# MODULE_CONTROL.net
KiCad netlist of a schematic drawn in Altium Designer
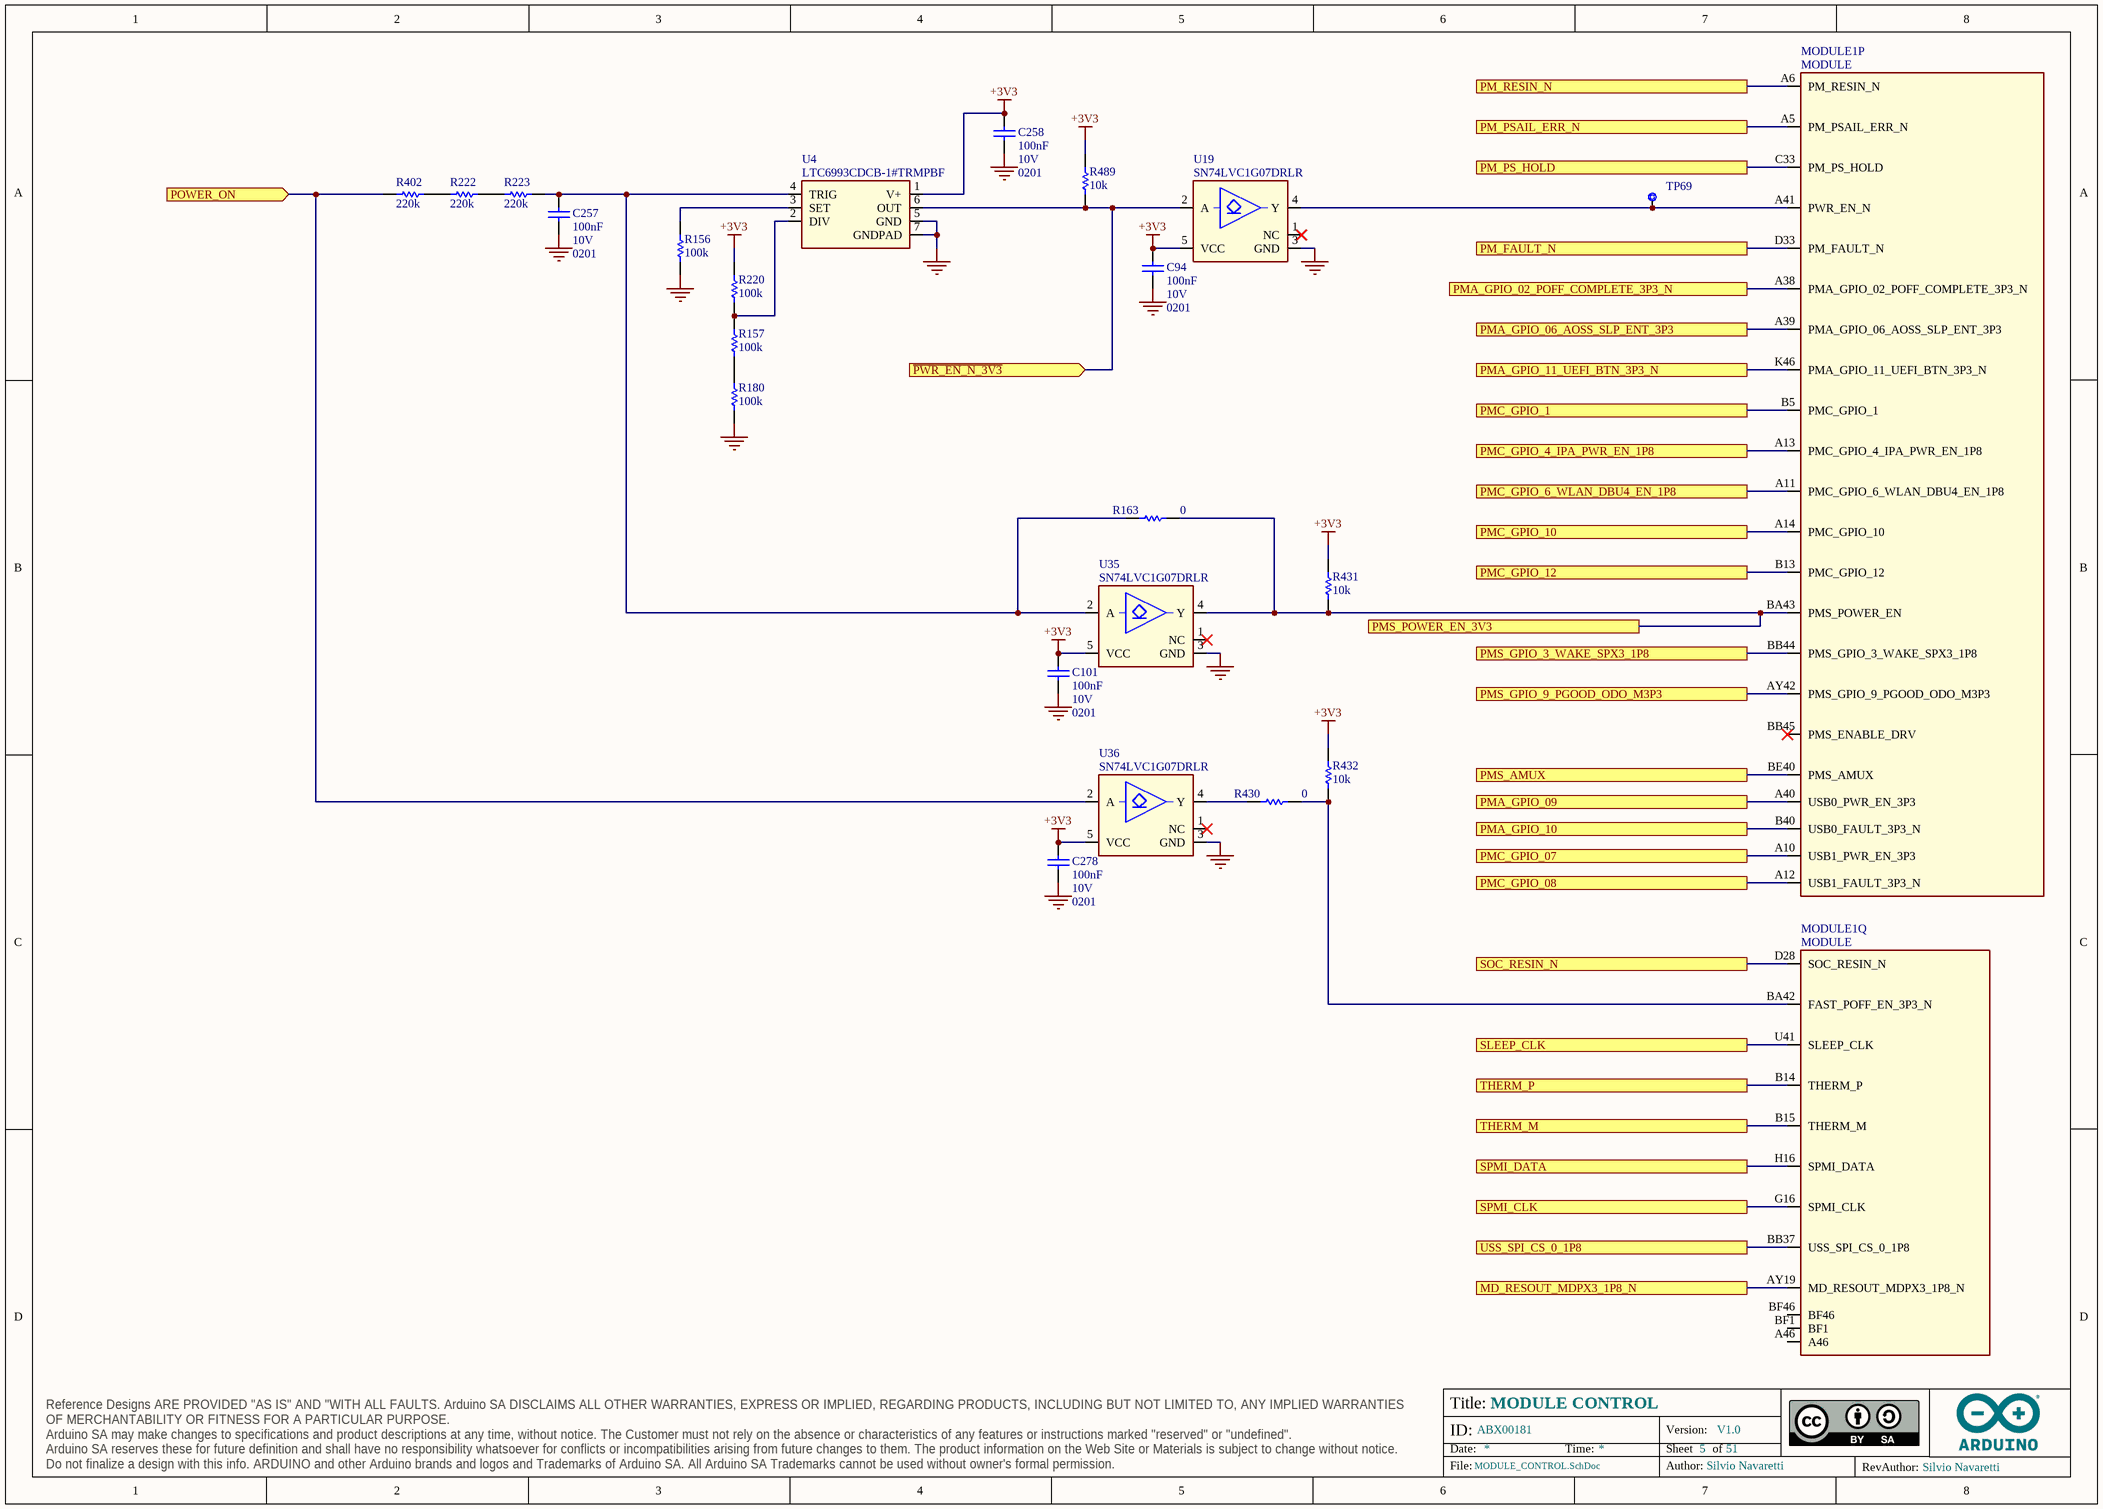
[diagram p0: MODULE_CONTROL.SchDoc]

(export (version "E")
  (design (tool "Eeschema 10.0.6"))
  (components
    (comp (ref "C94")
      (value "100nF")
      (footprint "CAP-0201")
      (description "CAP CHIP 0201 100nF 10% 10V X5R")
      (fields
        (field (name "PART NUMBER") "CL03A104KP3NNNC")
        (field (name "MANUFACTURER") "Samsung Electro-Mechanics")
        (field (name "VOLTAGE") "10V")
        (field (name "CASE CODE (IMPERIAL)") "0201")
      )
      (libsource (lib "Clean") (part "CAP"))
    )
    (comp (ref "C101")
      (value "100nF")
      (footprint "CAP-0201")
      (description "CAP CHIP 0201 100nF 10% 10V X5R")
      (fields
        (field (name "PART NUMBER") "CL03A104KP3NNNC")
        (field (name "MANUFACTURER") "Samsung Electro-Mechanics")
        (field (name "VOLTAGE") "10V")
        (field (name "CASE CODE (IMPERIAL)") "0201")
      )
      (libsource (lib "Clean") (part "CAP"))
    )
    (comp (ref "C257")
      (value "100nF")
      (footprint "CAP-0201")
      (description "CAP CHIP 0201 100nF 10% 10V X5R")
      (fields
        (field (name "PART NUMBER") "CL03A104KP3NNNC")
        (field (name "MANUFACTURER") "Samsung Electro-Mechanics")
        (field (name "VOLTAGE") "10V")
        (field (name "CASE CODE (IMPERIAL)") "0201")
      )
      (libsource (lib "Clean") (part "CAP"))
    )
    (comp (ref "C258")
      (value "100nF")
      (footprint "CAP-0201")
      (description "CAP CHIP 0201 100nF 10% 10V X5R")
      (fields
        (field (name "PART NUMBER") "CL03A104KP3NNNC")
        (field (name "MANUFACTURER") "Samsung Electro-Mechanics")
        (field (name "VOLTAGE") "10V")
        (field (name "CASE CODE (IMPERIAL)") "0201")
      )
      (libsource (lib "Clean") (part "CAP"))
    )
    (comp (ref "C278")
      (value "100nF")
      (footprint "CAP-0201")
      (description "CAP CHIP 0201 100nF 10% 10V X5R")
      (fields
        (field (name "PART NUMBER") "CL03A104KP3NNNC")
        (field (name "MANUFACTURER") "Samsung Electro-Mechanics")
        (field (name "VOLTAGE") "10V")
        (field (name "CASE CODE (IMPERIAL)") "0201")
      )
      (libsource (lib "Clean") (part "CAP"))
    )
    (comp (ref "MODULE1")
      (value "MODULE")
      (footprint "MODULE")
      (description "MODULE BGA 1883 balls 57.5x57.5mm")
      (fields (field (name "MANUFACTURER") "Qualcomm") (field (name "PART NUMBER") "MODULE BGA"))
      (libsource (lib "Clean") (part "MODULE"))
    )
    (comp (ref "R156")
      (value "100k")
      (footprint "RES-0201")
      (description "RES CHIP 0201 100k 1% 1/20W")
      (fields (field (name "POWER") "50mW") (field (name "TOLERANCE") "1%"))
      (libsource (lib "Clean") (part "RES"))
    )
    (comp (ref "R157")
      (value "100k")
      (footprint "RES-0201")
      (description "RES CHIP 0201 100k 1% 1/20W")
      (fields (field (name "POWER") "50mW") (field (name "TOLERANCE") "1%"))
      (libsource (lib "Clean") (part "RES"))
    )
    (comp (ref "R163")
      (value "0")
      (footprint "RES-0201")
      (description "RES CHIP 0201 0R")
      (fields (field (name "MANUFACTURER") "Vishay") (field (name "PART NUMBER") "CRCW02010000Z0ED"))
      (libsource (lib "Clean") (part "RES"))
    )
    (comp (ref "R180")
      (value "100k")
      (footprint "RES-0201")
      (description "RES CHIP 0201 100k 1% 1/20W")
      (fields (field (name "POWER") "50mW") (field (name "TOLERANCE") "1%"))
      (libsource (lib "Clean") (part "RES"))
    )
    (comp (ref "R220")
      (value "100k")
      (footprint "RES-0201")
      (description "RES CHIP 0201 100k 1% 1/20W")
      (fields (field (name "POWER") "50mW") (field (name "TOLERANCE") "1%"))
      (libsource (lib "Clean") (part "RES"))
    )
    (comp (ref "R222")
      (value "220k")
      (footprint "RES-0201")
      (description "RES CHIP 0201 220k 1% 1/20W")
      (fields (field (name "PART NUMBER") "AC0201FR-07220KL") (field (name "TOLERANCE") "1%"))
      (libsource (lib "Clean") (part "RES"))
    )
    (comp (ref "R223")
      (value "220k")
      (footprint "RES-0201")
      (description "RES CHIP 0201 220k 1% 1/20W")
      (fields (field (name "PART NUMBER") "AC0201FR-07220KL") (field (name "TOLERANCE") "1%"))
      (libsource (lib "Clean") (part "RES"))
    )
    (comp (ref "R402")
      (value "220k")
      (footprint "RES-0201")
      (description "RES CHIP 0201 220k 1% 1/20W")
      (fields (field (name "PART NUMBER") "AC0201FR-07220KL") (field (name "TOLERANCE") "1%"))
      (libsource (lib "Clean") (part "RES"))
    )
    (comp (ref "R430")
      (value "0")
      (footprint "RES-0201")
      (description "RES CHIP 0201 0R")
      (fields (field (name "MANUFACTURER") "Vishay") (field (name "PART NUMBER") "CRCW02010000Z0ED"))
      (libsource (lib "Clean") (part "RES"))
    )
    (comp (ref "R431")
      (value "10k")
      (footprint "RES-0201")
      (description "RES CHIP 0201 10k 1% 1/20W")
      (fields (field (name "POWER") "50mW") (field (name "TOLERANCE") "1%"))
      (libsource (lib "Clean") (part "RES"))
    )
    (comp (ref "R432")
      (value "10k")
      (footprint "RES-0201")
      (description "RES CHIP 0201 10k 1% 1/20W")
      (fields (field (name "POWER") "50mW") (field (name "TOLERANCE") "1%"))
      (libsource (lib "Clean") (part "RES"))
    )
    (comp (ref "R489")
      (value "10k")
      (footprint "RES-0201")
      (description "RES CHIP 0201 10k 1% 1/20W")
      (fields (field (name "POWER") "50mW") (field (name "TOLERANCE") "1%"))
      (libsource (lib "Clean") (part "RES"))
    )
    (comp (ref "TP69")
      (value "Test point 1.00mm")
      (footprint "TP-1.00MM")
      (fields (field (name "PART NUMBER") "This is not a component"))
      (libsource (lib "Clean") (part "TESTPOINT"))
    )
    (comp (ref "U4")
      (value "LTC6993CDCB-1#TRMPBF")
      (footprint "AD DCB DFN 6 pin 2x3mm pitch 0.5mm")
      (description "IC monostable multivibrator programmable pulse 1us to 33.6 DFN6 2x3mm")
      (fields (field (name "MANUFACTURER") "Analog Devices"))
      (libsource (lib "Clean") (part "LTC6993CDCB-1#TRMPBF"))
    )
    (comp (ref "U19")
      (value "SN74LVC1G07DRLR")
      (footprint "TI DRL DRL0005A")
      (description "IC buffer open drain, 1.65V to 5.5V, 32mA sink current, SOT-5X3 1.6mmx1.6mm")
      (fields (field (name "MANUFACTURER") "Texas Instruments"))
      (libsource (lib "Clean") (part "SN74LVC1G07DRLR"))
    )
    (comp (ref "U35")
      (value "SN74LVC1G07DRLR")
      (footprint "TI DRL DRL0005A")
      (description "IC buffer open drain, 1.65V to 5.5V, 32mA sink current, SOT-5X3 1.6mmx1.6mm")
      (fields (field (name "MANUFACTURER") "Texas Instruments"))
      (libsource (lib "Clean") (part "SN74LVC1G07DRLR"))
    )
    (comp (ref "U36")
      (value "SN74LVC1G07DRLR")
      (footprint "TI DRL DRL0005A")
      (description "IC buffer open drain, 1.65V to 5.5V, 32mA sink current, SOT-5X3 1.6mmx1.6mm")
      (fields (field (name "MANUFACTURER") "Texas Instruments"))
      (libsource (lib "Clean") (part "SN74LVC1G07DRLR"))
    )
  )
  (nets
    (net (code "1") (name "+3V3") (class "Default")
      (node (ref "C101") (pin "2") (pinfunction "2_2") (pintype "passive"))
      (node (ref "C258") (pin "2") (pinfunction "2_2") (pintype "passive"))
      (node (ref "C278") (pin "2") (pinfunction "2_2") (pintype "passive"))
      (node (ref "C94") (pin "2") (pinfunction "2_2") (pintype "passive"))
      (node (ref "R220") (pin "2") (pinfunction "2_2") (pintype "passive"))
      (node (ref "R431") (pin "1") (pinfunction "1_1") (pintype "passive"))
      (node (ref "R432") (pin "1") (pinfunction "1_1") (pintype "passive"))
      (node (ref "R489") (pin "1") (pinfunction "1_1") (pintype "passive"))
      (node (ref "U19") (pin "5") (pinfunction "VCC_5") (pintype "passive"))
      (node (ref "U35") (pin "5") (pinfunction "VCC_5") (pintype "passive"))
      (node (ref "U36") (pin "5") (pinfunction "VCC_5") (pintype "passive"))
      (node (ref "U4") (pin "1") (pinfunction "V+_1") (pintype "passive"))
    )
    (net (code "2") (name "/MD_RESOUT_MDPX3_1P8_N") (class "Default")
      (node (ref "MODULE1") (pin "AY19") (pinfunction "MD_RESOUT_MDPX3_1P8_N_AY19") (pintype "passive"))
    )
    (net (code "3") (name "/PMA_GPIO_02_POFF_COMPLETE_3P3_N") (class "Default")
      (node (ref "MODULE1") (pin "A38") (pinfunction "PMA_GPIO_02_POFF_COMPLETE_3P3_N_A38") (pintype "passive"))
    )
    (net (code "4") (name "/PMA_GPIO_06_AOSS_SLP_ENT_3P3") (class "Default")
      (node (ref "MODULE1") (pin "A39") (pinfunction "PMA_GPIO_06_AOSS_SLP_ENT_3P3_A39") (pintype "passive"))
    )
    (net (code "5") (name "/PMA_GPIO_09") (class "Default")
      (node (ref "MODULE1") (pin "A40") (pinfunction "USB0_PWR_EN_3P3_A40") (pintype "passive"))
    )
    (net (code "6") (name "/PMA_GPIO_10") (class "Default")
      (node (ref "MODULE1") (pin "B40") (pinfunction "USB0_FAULT_3P3_N_B40") (pintype "passive"))
    )
    (net (code "7") (name "/PMA_GPIO_11_UEFI_BTN_3P3_N") (class "Default")
      (node (ref "MODULE1") (pin "K46") (pinfunction "PMA_GPIO_11_UEFI_BTN_3P3_N_K46") (pintype "passive"))
    )
    (net (code "8") (name "/PMC_GPIO_1") (class "Default")
      (node (ref "MODULE1") (pin "B5") (pinfunction "PMC_GPIO_1_B5") (pintype "passive"))
    )
    (net (code "9") (name "/PMC_GPIO_4_IPA_PWR_EN_1P8") (class "Default")
      (node (ref "MODULE1") (pin "A13") (pinfunction "PMC_GPIO_4_IPA_PWR_EN_1P8_A13") (pintype "passive"))
    )
    (net (code "10") (name "/PMC_GPIO_6_WLAN_DBU4_EN_1P8") (class "Default")
      (node (ref "MODULE1") (pin "A11") (pinfunction "PMC_GPIO_6_WLAN_DBU4_EN_1P8_A11") (pintype "passive"))
    )
    (net (code "11") (name "/PMC_GPIO_07") (class "Default")
      (node (ref "MODULE1") (pin "A10") (pinfunction "USB1_PWR_EN_3P3_A10") (pintype "passive"))
    )
    (net (code "12") (name "/PMC_GPIO_08") (class "Default")
      (node (ref "MODULE1") (pin "A12") (pinfunction "USB1_FAULT_3P3_N_A12") (pintype "passive"))
    )
    (net (code "13") (name "/PMC_GPIO_10") (class "Default")
      (node (ref "MODULE1") (pin "A14") (pinfunction "PMC_GPIO_10_A14") (pintype "passive"))
    )
    (net (code "14") (name "/PMC_GPIO_12") (class "Default")
      (node (ref "MODULE1") (pin "B13") (pinfunction "PMC_GPIO_12_B13") (pintype "passive"))
    )
    (net (code "15") (name "/PMS_AMUX") (class "Default")
      (node (ref "MODULE1") (pin "BE40") (pinfunction "PMS_AMUX_BE40") (pintype "passive"))
    )
    (net (code "16") (name "/PMS_GPIO_3_WAKE_SPX3_1P8") (class "Default")
      (node (ref "MODULE1") (pin "BB44") (pinfunction "PMS_GPIO_3_WAKE_SPX3_1P8_BB44") (pintype "passive"))
    )
    (net (code "17") (name "/PMS_GPIO_9_PGOOD_ODO_M3P3") (class "Default")
      (node (ref "MODULE1") (pin "AY42") (pinfunction "PMS_GPIO_9_PGOOD_ODO_M3P3_AY42") (pintype "passive"))
    )
    (net (code "18") (name "/PMS_POWER_EN_3V3") (class "Default")
      (node (ref "MODULE1") (pin "BA43") (pinfunction "PMS_POWER_EN_BA43") (pintype "passive"))
      (node (ref "R163") (pin "1") (pinfunction "1_1") (pintype "passive"))
      (node (ref "R431") (pin "2") (pinfunction "2_2") (pintype "passive"))
      (node (ref "U35") (pin "4") (pinfunction "Y_4") (pintype "passive"))
    )
    (net (code "19") (name "/PM_FAULT_N") (class "Default")
      (node (ref "MODULE1") (pin "D33") (pinfunction "PM_FAULT_N_D33") (pintype "passive"))
    )
    (net (code "20") (name "/PM_PSAIL_ERR_N") (class "Default")
      (node (ref "MODULE1") (pin "A5") (pinfunction "PM_PSAIL_ERR_N_A5") (pintype "passive"))
    )
    (net (code "21") (name "/PM_PS_HOLD") (class "Default")
      (node (ref "MODULE1") (pin "C33") (pinfunction "PM_PS_HOLD_C33") (pintype "passive"))
    )
    (net (code "22") (name "/PM_RESIN_N") (class "Default")
      (node (ref "MODULE1") (pin "A6") (pinfunction "PM_RESIN_N_A6") (pintype "passive"))
    )
    (net (code "23") (name "/POWER_ON") (class "Default")
      (node (ref "R402") (pin "2") (pinfunction "2_2") (pintype "passive"))
      (node (ref "U36") (pin "2") (pinfunction "A_2") (pintype "passive"))
    )
    (net (code "24") (name "/SLEEP_CLK") (class "Default")
      (node (ref "MODULE1") (pin "U41") (pinfunction "SLEEP_CLK_U41") (pintype "passive"))
    )
    (net (code "25") (name "/SOC_RESIN_N") (class "Default")
      (node (ref "MODULE1") (pin "D28") (pinfunction "SOC_RESIN_N_D28") (pintype "passive"))
    )
    (net (code "26") (name "/SPMI_CLK") (class "Default")
      (node (ref "MODULE1") (pin "G16") (pinfunction "SPMI_CLK_G16") (pintype "passive"))
    )
    (net (code "27") (name "/SPMI_DATA") (class "Default")
      (node (ref "MODULE1") (pin "H16") (pinfunction "SPMI_DATA_H16") (pintype "passive"))
    )
    (net (code "28") (name "/THERM_M") (class "Default")
      (node (ref "MODULE1") (pin "B15") (pinfunction "THERM_M_B15") (pintype "passive"))
    )
    (net (code "29") (name "/THERM_P") (class "Default")
      (node (ref "MODULE1") (pin "B14") (pinfunction "THERM_P_B14") (pintype "passive"))
    )
    (net (code "30") (name "/USS_SPI_CS_0_1P8") (class "Default")
      (node (ref "MODULE1") (pin "BB37") (pinfunction "USS_SPI_CS_0_1P8_BB37") (pintype "passive"))
    )
    (net (code "31") (name "/~{PWR_EN_N_3V3}") (class "Default")
      (node (ref "R489") (pin "2") (pinfunction "2_2") (pintype "passive"))
      (node (ref "U19") (pin "2") (pinfunction "A_2") (pintype "passive"))
      (node (ref "U4") (pin "6") (pinfunction "OUT_6") (pintype "passive"))
    )
    (net (code "32") (name "GND") (class "Default")
      (node (ref "C101") (pin "1") (pinfunction "1_1") (pintype "passive"))
      (node (ref "C257") (pin "1") (pinfunction "1_1") (pintype "passive"))
      (node (ref "C258") (pin "1") (pinfunction "1_1") (pintype "passive"))
      (node (ref "C278") (pin "1") (pinfunction "1_1") (pintype "passive"))
      (node (ref "C94") (pin "1") (pinfunction "1_1") (pintype "passive"))
      (node (ref "R156") (pin "1") (pinfunction "1_1") (pintype "passive"))
      (node (ref "R180") (pin "1") (pinfunction "1_1") (pintype "passive"))
      (node (ref "U19") (pin "3") (pinfunction "GND_3") (pintype "passive"))
      (node (ref "U35") (pin "3") (pinfunction "GND_3") (pintype "passive"))
      (node (ref "U36") (pin "3") (pinfunction "GND_3") (pintype "passive"))
      (node (ref "U4") (pin "5") (pinfunction "GND_5") (pintype "passive"))
      (node (ref "U4") (pin "7") (pinfunction "GNDPAD_7") (pintype "passive"))
    )
    (net (code "33") (name "Net-(MODULE1P-PWR_EN_N)") (class "Default")
      (node (ref "MODULE1") (pin "A41") (pinfunction "PWR_EN_N_A41") (pintype "passive"))
      (node (ref "TP69") (pin "X") (pinfunction "X_X") (pintype "passive"))
      (node (ref "U19") (pin "4") (pinfunction "Y_4") (pintype "passive"))
    )
    (net (code "34") (name "Net-(MODULE1Q-FAST_POFF_EN_3P3_N)") (class "Default")
      (node (ref "MODULE1") (pin "BA42") (pinfunction "FAST_POFF_EN_3P3_N_BA42") (pintype "passive"))
      (node (ref "R430") (pin "1") (pinfunction "1_1") (pintype "passive"))
      (node (ref "R432") (pin "2") (pinfunction "2_2") (pintype "passive"))
    )
    (net (code "35") (name "Net-(R157-Pad1)") (class "Default")
      (node (ref "R157") (pin "1") (pinfunction "1_1") (pintype "passive"))
      (node (ref "R180") (pin "2") (pinfunction "2_2") (pintype "passive"))
    )
    (net (code "36") (name "Net-(R222-Pad1)") (class "Default")
      (node (ref "R222") (pin "1") (pinfunction "1_1") (pintype "passive"))
      (node (ref "R223") (pin "2") (pinfunction "2_2") (pintype "passive"))
    )
    (net (code "37") (name "Net-(R222-Pad2)") (class "Default")
      (node (ref "R222") (pin "2") (pinfunction "2_2") (pintype "passive"))
      (node (ref "R402") (pin "1") (pinfunction "1_1") (pintype "passive"))
    )
    (net (code "38") (name "Net-(U4-DIV)") (class "Default")
      (node (ref "R157") (pin "2") (pinfunction "2_2") (pintype "passive"))
      (node (ref "R220") (pin "1") (pinfunction "1_1") (pintype "passive"))
      (node (ref "U4") (pin "2") (pinfunction "DIV_2") (pintype "passive"))
    )
    (net (code "39") (name "Net-(U4-SET)") (class "Default")
      (node (ref "R156") (pin "2") (pinfunction "2_2") (pintype "passive"))
      (node (ref "U4") (pin "3") (pinfunction "SET_3") (pintype "passive"))
    )
    (net (code "40") (name "Net-(U35-A)") (class "Default")
      (node (ref "C257") (pin "2") (pinfunction "2_2") (pintype "passive"))
      (node (ref "R163") (pin "2") (pinfunction "2_2") (pintype "passive"))
      (node (ref "R223") (pin "1") (pinfunction "1_1") (pintype "passive"))
      (node (ref "U35") (pin "2") (pinfunction "A_2") (pintype "passive"))
      (node (ref "U4") (pin "4") (pinfunction "TRIG_4") (pintype "passive"))
    )
    (net (code "41") (name "Net-(U36-Y)") (class "Default")
      (node (ref "R430") (pin "2") (pinfunction "2_2") (pintype "passive"))
      (node (ref "U36") (pin "4") (pinfunction "Y_4") (pintype "passive"))
    )
    (net (code "42") (name "unconnected-(MODULE1-PadA46)") (class "Default")
      (node (ref "MODULE1") (pin "A46") (pinfunction "A46_A46") (pintype "passive"))
    )
    (net (code "43") (name "unconnected-(MODULE1-PadBF1)") (class "Default")
      (node (ref "MODULE1") (pin "BF1") (pinfunction "BF1_BF1") (pintype "passive"))
    )
    (net (code "44") (name "unconnected-(MODULE1-PadBF46)") (class "Default")
      (node (ref "MODULE1") (pin "BF46") (pinfunction "BF46_BF46") (pintype "passive"))
    )
    (net (code "45") (name "unconnected-(MODULE1P-PMS_ENABLE_DRV-PadBB45)") (class "Default")
      (node (ref "MODULE1") (pin "BB45") (pinfunction "PMS_ENABLE_DRV_BB45") (pintype "passive+no_connect"))
    )
    (net (code "46") (name "unconnected-(U19-NC-Pad1)") (class "Default")
      (node (ref "U19") (pin "1") (pinfunction "NC_1") (pintype "passive+no_connect"))
    )
    (net (code "47") (name "unconnected-(U35-NC-Pad1)") (class "Default")
      (node (ref "U35") (pin "1") (pinfunction "NC_1") (pintype "passive+no_connect"))
    )
    (net (code "48") (name "unconnected-(U36-NC-Pad1)") (class "Default")
      (node (ref "U36") (pin "1") (pinfunction "NC_1") (pintype "passive+no_connect"))
    )
  )
)
